# EX1.net
KiCad netlist of a schematic drawn in Altium Designer
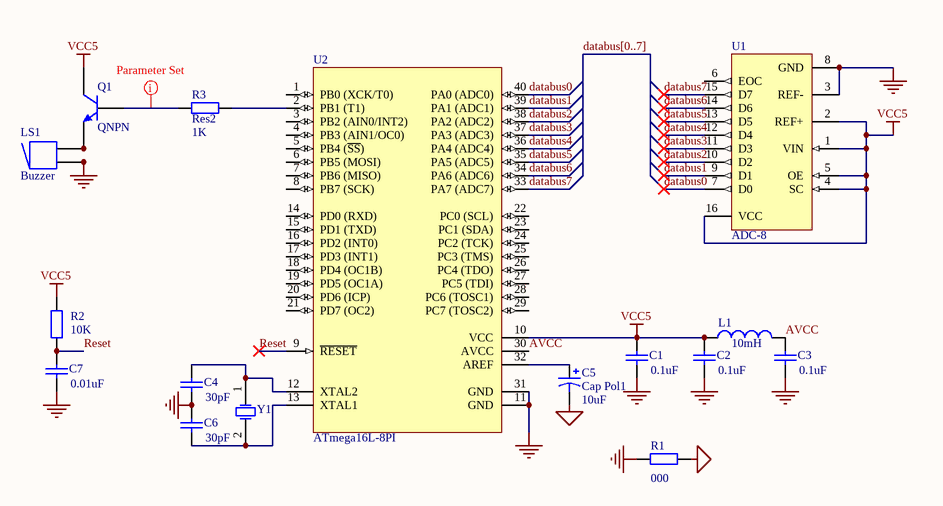
[diagram p0: EX1.SchDoc]

(export (version "E")
  (design (tool "Eeschema 10.0.6"))
  (components
    (comp (ref "C1")
      (value "0.1uF")
      (footprint "C0805")
      (description "Capacitor")
      (fields (field (name "Comment") "Cap") (field (name "PUBLISHER") "Altium Limited"))
      (libsource (lib "Miscellaneous Devices") (part "Cap"))
    )
    (comp (ref "C2")
      (value "0.1uF")
      (footprint "C0805")
      (description "Capacitor")
      (fields (field (name "Comment") "Cap") (field (name "PUBLISHER") "Altium Limited"))
      (libsource (lib "Miscellaneous Devices") (part "Cap"))
    )
    (comp (ref "C3")
      (value "0.1uF")
      (footprint "C0805")
      (description "Capacitor")
      (fields (field (name "Comment") "Cap") (field (name "PUBLISHER") "Altium Limited"))
      (libsource (lib "Miscellaneous Devices") (part "Cap"))
    )
    (comp (ref "C4")
      (value "30pF")
      (footprint "C0805")
      (description "Capacitor")
      (fields (field (name "Comment") "Cap") (field (name "PUBLISHER") "Altium Limited"))
      (libsource (lib "Miscellaneous Devices") (part "Cap"))
    )
    (comp (ref "C5")
      (value "Cap Pol1")
      (footprint "RB7.6-15")
      (description "Polarized Capacitor (Radial)")
      (fields (field (name "ALTIUM_VALUE") "10uF") (field (name "PUBLISHER") "Altium Limited"))
      (libsource (lib "Miscellaneous Devices") (part "Cap Pol1"))
    )
    (comp (ref "C6")
      (value "30pF")
      (footprint "C0805")
      (description "Capacitor")
      (fields (field (name "Comment") "Cap") (field (name "PUBLISHER") "Altium Limited"))
      (libsource (lib "Miscellaneous Devices") (part "Cap"))
    )
    (comp (ref "C7")
      (value "0.01uF")
      (footprint "C0805")
      (description "Capacitor")
      (fields (field (name "Comment") "Cap") (field (name "PUBLISHER") "Altium Limited"))
      (libsource (lib "Miscellaneous Devices") (part "Cap"))
    )
    (comp (ref "L1")
      (value "10mH")
      (footprint "C0805")
      (description "Inductor")
      (fields (field (name "PUBLISHER") "Altium Limited"))
      (libsource (lib "Miscellaneous Devices") (part "Inductor"))
    )
    (comp (ref "LS1")
      (value "Buzzer")
      (footprint "ABSM-1574")
      (description "Magnetic Transducer Buzzer")
      (fields (field (name "PUBLISHER") "Altium Limited"))
      (libsource (lib "Miscellaneous Devices") (part "Buzzer"))
    )
    (comp (ref "Q1")
      (value "QNPN")
      (footprint "SOT-23B_N")
      (description "NPN Bipolar Transistor")
      (fields (field (name "PUBLISHER") "Altium Limited"))
      (libsource (lib "Miscellaneous Devices") (part "QNPN"))
    )
    (comp (ref "R1")
      (value "000")
      (footprint "6-0805_N")
      (description "Resistor")
      (fields (field (name "Comment") "Res2") (field (name "PUBLISHER") "Altium Limited"))
      (libsource (lib "Miscellaneous Devices") (part "Res2"))
    )
    (comp (ref "R2")
      (value "10K")
      (footprint "6-0805_N")
      (description "Resistor")
      (fields (field (name "Comment") "Res2") (field (name "PUBLISHER") "Altium Limited"))
      (libsource (lib "") (part "Res2_1"))
    )
    (comp (ref "R3")
      (value "Res2")
      (footprint "6-0805_N")
      (description "Resistor")
      (fields (field (name "ALTIUM_VALUE") "1K") (field (name "PUBLISHER") "Altium Limited"))
      (libsource (lib "Miscellaneous Devices") (part "Res2"))
    )
    (comp (ref "U1")
      (value "ADC-8")
      (footprint "SOT403-1_N")
      (description "Generic 8-Bit A/D Converter")
      (fields (field (name "PUBLISHER") "Altium Limited"))
      (libsource (lib "Miscellaneous Devices") (part "ADC-8"))
    )
    (comp (ref "U2")
      (value "ATmega16L-8PI")
      (footprint "40P6")
      (description "8-Bit AVR Microcontroller with 16K Bytes of In-System Programmable Flash Memory")
      (fields (field (name "PUBLISHER") "Altium Limited"))
      (libsource (lib "Atmel Microcontroller 8-Bit AVR") (part "ATmega16L-8PI"))
    )
    (comp (ref "Y1")
      (value "XTAL")
      (footprint "R38")
      (description "Crystal Oscillator")
      (fields (field (name "PUBLISHER") "Altium Limited"))
      (libsource (lib "Miscellaneous Devices") (part "XTAL"))
    )
  )
  (nets
    (net (code "1") (name "/AVCC") (class "Default")
      (node (ref "C3") (pin "2") (pinfunction "2_2") (pintype "passive"))
      (node (ref "L1") (pin "2") (pinfunction "2_2") (pintype "passive"))
      (node (ref "U2") (pin "30") (pinfunction "AVCC_30") (pintype "power_in"))
    )
    (net (code "2") (name "/Reset") (class "Default")
      (node (ref "C7") (pin "1") (pinfunction "1_1") (pintype "passive"))
      (node (ref "R2") (pin "1") (pinfunction "1_1") (pintype "passive"))
      (node (ref "U2") (pin "9") (pinfunction "~{RESET}_9") (pintype "input"))
    )
    (net (code "3") (name "/databus0") (class "Default")
      (node (ref "U1") (pin "7") (pinfunction "D0_7") (pintype "output"))
      (node (ref "U2") (pin "40") (pinfunction "PA0_(ADC0)_40") (pintype "bidirectional"))
    )
    (net (code "4") (name "/databus1") (class "Default")
      (node (ref "U1") (pin "9") (pinfunction "D1_9") (pintype "output"))
      (node (ref "U2") (pin "39") (pinfunction "PA1_(ADC1)_39") (pintype "bidirectional"))
    )
    (net (code "5") (name "/databus2") (class "Default")
      (node (ref "U1") (pin "10") (pinfunction "D2_10") (pintype "output"))
      (node (ref "U2") (pin "38") (pinfunction "PA2_(ADC2)_38") (pintype "bidirectional"))
    )
    (net (code "6") (name "/databus3") (class "Default")
      (node (ref "U1") (pin "11") (pinfunction "D3_11") (pintype "output"))
      (node (ref "U2") (pin "37") (pinfunction "PA3_(ADC3)_37") (pintype "bidirectional"))
    )
    (net (code "7") (name "/databus4") (class "Default")
      (node (ref "U1") (pin "12") (pinfunction "D4_12") (pintype "output"))
      (node (ref "U2") (pin "36") (pinfunction "PA4_(ADC4)_36") (pintype "bidirectional"))
    )
    (net (code "8") (name "/databus5") (class "Default")
      (node (ref "U1") (pin "13") (pinfunction "D5_13") (pintype "output"))
      (node (ref "U2") (pin "35") (pinfunction "PA5_(ADC5)_35") (pintype "bidirectional"))
    )
    (net (code "9") (name "/databus6") (class "Default")
      (node (ref "U1") (pin "14") (pinfunction "D6_14") (pintype "output"))
      (node (ref "U2") (pin "34") (pinfunction "PA6_(ADC6)_34") (pintype "bidirectional"))
    )
    (net (code "10") (name "/databus7") (class "Default")
      (node (ref "U1") (pin "15") (pinfunction "D7_15") (pintype "output"))
      (node (ref "U2") (pin "33") (pinfunction "PA7_(ADC7)_33") (pintype "bidirectional"))
    )
    (net (code "12") (name "AGND") (class "Default")
      (node (ref "C5") (pin "2") (pinfunction "2_2") (pintype "passive"))
      (node (ref "R1") (pin "2") (pinfunction "2_2") (pintype "passive"))
    )
    (net (code "13") (name "GND") (class "Default")
      (node (ref "C1") (pin "1") (pinfunction "1_1") (pintype "passive"))
      (node (ref "C2") (pin "1") (pinfunction "1_1") (pintype "passive"))
      (node (ref "C3") (pin "1") (pinfunction "1_1") (pintype "passive"))
      (node (ref "C4") (pin "1") (pinfunction "1_1") (pintype "passive"))
      (node (ref "C6") (pin "2") (pinfunction "2_2") (pintype "passive"))
      (node (ref "C7") (pin "2") (pinfunction "2_2") (pintype "passive"))
      (node (ref "LS1") (pin "1") (pinfunction "1_1") (pintype "passive"))
      (node (ref "LS1") (pin "1A") (pinfunction "1A_1A") (pintype "passive"))
      (node (ref "R1") (pin "1") (pinfunction "1_1") (pintype "passive"))
      (node (ref "U1") (pin "3") (pinfunction "REF-_3") (pintype "passive"))
      (node (ref "U1") (pin "8") (pinfunction "GND_8") (pintype "power_in"))
      (node (ref "U2") (pin "11") (pinfunction "GND_11") (pintype "power_in"))
      (node (ref "U2") (pin "31") (pinfunction "GND_31") (pintype "power_in"))
    )
    (net (code "14") (name "Net-(Q1-B)") (class "Default")
      (node (ref "Q1") (pin "2") (pinfunction "B_2") (pintype "passive"))
      (node (ref "R3") (pin "1") (pinfunction "1_1") (pintype "passive"))
    )
    (net (code "15") (name "Net-(Q1-E)") (class "Default")
      (node (ref "LS1") (pin "2") (pinfunction "2_2") (pintype "passive"))
      (node (ref "LS1") (pin "2A") (pinfunction "2A_2A") (pintype "passive"))
      (node (ref "Q1") (pin "3") (pinfunction "E_3") (pintype "passive"))
    )
    (net (code "16") (name "Net-(U2-AREF)") (class "Default")
      (node (ref "C5") (pin "1") (pinfunction "1_1") (pintype "passive"))
      (node (ref "U2") (pin "32") (pinfunction "AREF_32") (pintype "passive"))
    )
    (net (code "17") (name "Net-(U2-PB1_(T1))") (class "Default")
      (node (ref "R3") (pin "2") (pinfunction "2_2") (pintype "passive"))
      (node (ref "U2") (pin "2") (pinfunction "PB1_(T1)_2") (pintype "bidirectional"))
    )
    (net (code "18") (name "Net-(U2-XTAL1)") (class "Default")
      (node (ref "C6") (pin "1") (pinfunction "1_1") (pintype "passive"))
      (node (ref "U2") (pin "13") (pinfunction "XTAL1_13") (pintype "passive"))
      (node (ref "Y1") (pin "2") (pinfunction "OSC2_2") (pintype "passive"))
    )
    (net (code "19") (name "Net-(U2-XTAL2)") (class "Default")
      (node (ref "C4") (pin "2") (pinfunction "2_2") (pintype "passive"))
      (node (ref "U2") (pin "12") (pinfunction "XTAL2_12") (pintype "passive"))
      (node (ref "Y1") (pin "1") (pinfunction "OSC1_1") (pintype "passive"))
    )
    (net (code "20") (name "VCC5") (class "Default")
      (node (ref "C1") (pin "2") (pinfunction "2_2") (pintype "passive"))
      (node (ref "C2") (pin "2") (pinfunction "2_2") (pintype "passive"))
      (node (ref "L1") (pin "1") (pinfunction "1_1") (pintype "passive"))
      (node (ref "Q1") (pin "1") (pinfunction "C_1") (pintype "passive"))
      (node (ref "R2") (pin "2") (pinfunction "2_2") (pintype "passive"))
      (node (ref "U1") (pin "1") (pinfunction "VIN_1") (pintype "input"))
      (node (ref "U1") (pin "16") (pinfunction "VCC_16") (pintype "power_in"))
      (node (ref "U1") (pin "2") (pinfunction "REF+_2") (pintype "passive"))
      (node (ref "U1") (pin "4") (pinfunction "SC_4") (pintype "input"))
      (node (ref "U1") (pin "5") (pinfunction "OE_5") (pintype "input"))
      (node (ref "U2") (pin "10") (pinfunction "VCC_10") (pintype "power_in"))
    )
    (net (code "21") (name "unconnected-(U1-EOC-Pad6)") (class "Default")
      (node (ref "U1") (pin "6") (pinfunction "EOC_6") (pintype "output"))
    )
    (net (code "22") (name "unconnected-(U2-PB0_(XCK{slash}T0)-Pad1)") (class "Default")
      (node (ref "U2") (pin "1") (pinfunction "PB0_(XCK/T0)_1") (pintype "bidirectional"))
    )
    (net (code "23") (name "unconnected-(U2-PB2_(AIN0{slash}INT2)-Pad3)") (class "Default")
      (node (ref "U2") (pin "3") (pinfunction "PB2_(AIN0/INT2)_3") (pintype "bidirectional"))
    )
    (net (code "24") (name "unconnected-(U2-PB3_(AIN1{slash}OC0)-Pad4)") (class "Default")
      (node (ref "U2") (pin "4") (pinfunction "PB3_(AIN1/OC0)_4") (pintype "bidirectional"))
    )
    (net (code "25") (name "unconnected-(U2-PB4_(~{SS})-Pad5)") (class "Default")
      (node (ref "U2") (pin "5") (pinfunction "PB4_(~{SS})_5") (pintype "bidirectional"))
    )
    (net (code "26") (name "unconnected-(U2-PB5_(MOSI)-Pad6)") (class "Default")
      (node (ref "U2") (pin "6") (pinfunction "PB5_(MOSI)_6") (pintype "bidirectional"))
    )
    (net (code "27") (name "unconnected-(U2-PB6_(MISO)-Pad7)") (class "Default")
      (node (ref "U2") (pin "7") (pinfunction "PB6_(MISO)_7") (pintype "bidirectional"))
    )
    (net (code "28") (name "unconnected-(U2-PB7_(SCK)-Pad8)") (class "Default")
      (node (ref "U2") (pin "8") (pinfunction "PB7_(SCK)_8") (pintype "bidirectional"))
    )
    (net (code "29") (name "unconnected-(U2-PC0_(SCL)-Pad22)") (class "Default")
      (node (ref "U2") (pin "22") (pinfunction "PC0_(SCL)_22") (pintype "bidirectional"))
    )
    (net (code "30") (name "unconnected-(U2-PC1_(SDA)-Pad23)") (class "Default")
      (node (ref "U2") (pin "23") (pinfunction "PC1_(SDA)_23") (pintype "bidirectional"))
    )
    (net (code "31") (name "unconnected-(U2-PC2_(TCK)-Pad24)") (class "Default")
      (node (ref "U2") (pin "24") (pinfunction "PC2_(TCK)_24") (pintype "bidirectional"))
    )
    (net (code "32") (name "unconnected-(U2-PC3_(TMS)-Pad25)") (class "Default")
      (node (ref "U2") (pin "25") (pinfunction "PC3_(TMS)_25") (pintype "bidirectional"))
    )
    (net (code "33") (name "unconnected-(U2-PC4_(TDO)-Pad26)") (class "Default")
      (node (ref "U2") (pin "26") (pinfunction "PC4_(TDO)_26") (pintype "bidirectional"))
    )
    (net (code "34") (name "unconnected-(U2-PC5_(TDI)-Pad27)") (class "Default")
      (node (ref "U2") (pin "27") (pinfunction "PC5_(TDI)_27") (pintype "bidirectional"))
    )
    (net (code "35") (name "unconnected-(U2-PC6_(TOSC1)-Pad28)") (class "Default")
      (node (ref "U2") (pin "28") (pinfunction "PC6_(TOSC1)_28") (pintype "bidirectional"))
    )
    (net (code "36") (name "unconnected-(U2-PC7_(TOSC2)-Pad29)") (class "Default")
      (node (ref "U2") (pin "29") (pinfunction "PC7_(TOSC2)_29") (pintype "bidirectional"))
    )
    (net (code "37") (name "unconnected-(U2-PD0_(RXD)-Pad14)") (class "Default")
      (node (ref "U2") (pin "14") (pinfunction "PD0_(RXD)_14") (pintype "bidirectional"))
    )
    (net (code "38") (name "unconnected-(U2-PD1_(TXD)-Pad15)") (class "Default")
      (node (ref "U2") (pin "15") (pinfunction "PD1_(TXD)_15") (pintype "bidirectional"))
    )
    (net (code "39") (name "unconnected-(U2-PD2_(INT0)-Pad16)") (class "Default")
      (node (ref "U2") (pin "16") (pinfunction "PD2_(INT0)_16") (pintype "bidirectional"))
    )
    (net (code "40") (name "unconnected-(U2-PD3_(INT1)-Pad17)") (class "Default")
      (node (ref "U2") (pin "17") (pinfunction "PD3_(INT1)_17") (pintype "bidirectional"))
    )
    (net (code "41") (name "unconnected-(U2-PD4_(OC1B)-Pad18)") (class "Default")
      (node (ref "U2") (pin "18") (pinfunction "PD4_(OC1B)_18") (pintype "bidirectional"))
    )
    (net (code "42") (name "unconnected-(U2-PD5_(OC1A)-Pad19)") (class "Default")
      (node (ref "U2") (pin "19") (pinfunction "PD5_(OC1A)_19") (pintype "bidirectional"))
    )
    (net (code "43") (name "unconnected-(U2-PD6_(ICP)-Pad20)") (class "Default")
      (node (ref "U2") (pin "20") (pinfunction "PD6_(ICP)_20") (pintype "bidirectional"))
    )
    (net (code "44") (name "unconnected-(U2-PD7_(OC2)-Pad21)") (class "Default")
      (node (ref "U2") (pin "21") (pinfunction "PD7_(OC2)_21") (pintype "bidirectional"))
    )
  )
)
